# DAC_AK4493SEQ.net
KiCad netlist of a schematic drawn in Altium Designer
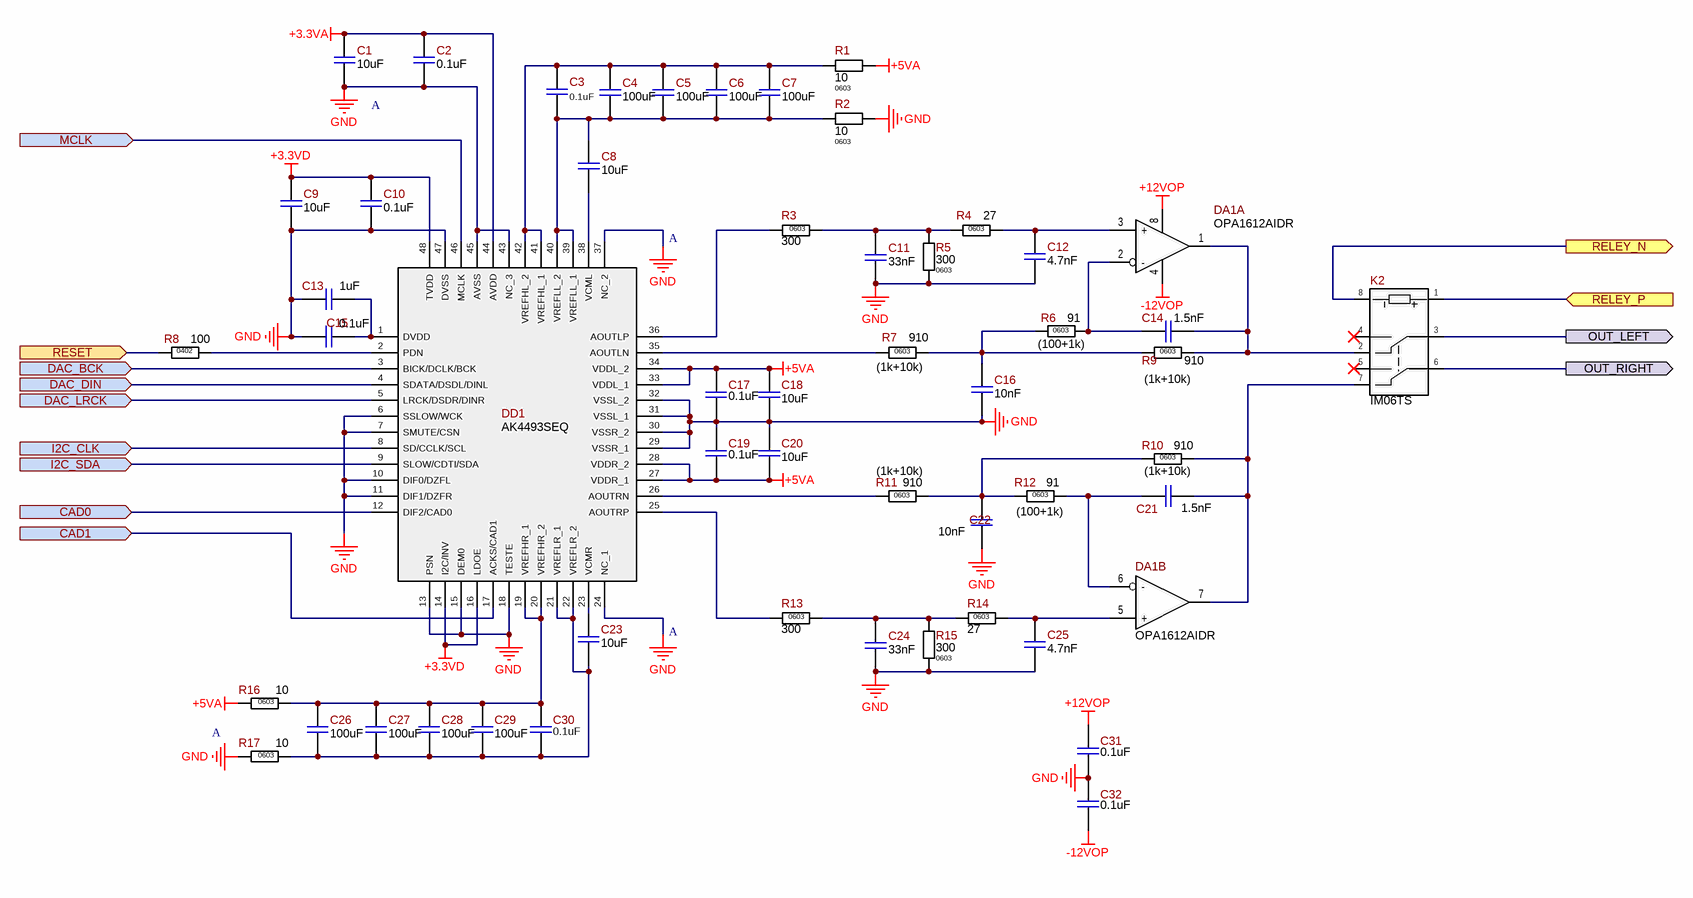
[diagram p0: DAC_AK4493SEQ.SchDoc]

(export (version "E")
  (design (tool "Eeschema 10.0.6"))
  (components
    (comp (ref "C1")
      (value "10uF")
      (footprint "C0402(1005)")
      (description "CAP CER 10UF 6.3V X6S 0402")
      (fields (field (name "PART NUMBER") "10uF  6.3V C0402") (field (name "TOLERANCE") "±20%"))
      (libsource (lib "Database") (part "Capacitor_Ceramic"))
    )
    (comp (ref "C2")
      (value "0.1uF")
      (footprint "C0402(1005)")
      (description "CAP CER 0.1UF 25V X7R 0603")
      (fields (field (name "PART NUMBER") "0.1uF  25V C0403") (field (name "TOLERANCE") "±10%"))
      (libsource (lib "Database") (part "Capacitor_Ceramic"))
    )
    (comp (ref "C3")
      (value "0.1uF")
      (footprint "C0402(1005)")
      (description "CAP CER 0.1UF 25V X7R 0603")
      (fields (field (name "PART NUMBER") "0.1uF  25V C0403") (field (name "TOLERANCE") "±10%"))
      (libsource (lib "Database") (part "Capacitor_Ceramic"))
    )
    (comp (ref "C4")
      (value "100uF")
      (footprint "C1206(3216)")
      (description "CAP CER 100UF 10V X5T 1206")
      (fields (field (name "PART NUMBER") "100uF  10V С1206") (field (name "TOLERANCE") "±20%"))
      (libsource (lib "Database") (part "Capacitor_Ceramic"))
    )
    (comp (ref "C5")
      (value "100uF")
      (footprint "C1206(3216)")
      (description "CAP CER 100UF 10V X5T 1206")
      (fields (field (name "PART NUMBER") "100uF  10V С1206") (field (name "TOLERANCE") "±20%"))
      (libsource (lib "Database") (part "Capacitor_Ceramic"))
    )
    (comp (ref "C6")
      (value "100uF")
      (footprint "C1206(3216)")
      (description "CAP CER 100UF 10V X5T 1206")
      (fields (field (name "PART NUMBER") "100uF  10V С1206") (field (name "TOLERANCE") "±20%"))
      (libsource (lib "Database") (part "Capacitor_Ceramic"))
    )
    (comp (ref "C7")
      (value "100uF")
      (footprint "C1206(3216)")
      (description "CAP CER 100UF 10V X5T 1206")
      (fields (field (name "PART NUMBER") "100uF  10V С1206") (field (name "TOLERANCE") "±20%"))
      (libsource (lib "Database") (part "Capacitor_Ceramic"))
    )
    (comp (ref "C8")
      (value "10uF")
      (footprint "C0402(1005)")
      (description "CAP CER 10UF 6.3V X6S 0402")
      (fields (field (name "PART NUMBER") "10uF  6.3V C0402") (field (name "TOLERANCE") "±20%"))
      (libsource (lib "Database") (part "Capacitor_Ceramic"))
    )
    (comp (ref "C9")
      (value "10uF")
      (footprint "C0402(1005)")
      (description "CAP CER 10UF 6.3V X6S 0402")
      (fields (field (name "PART NUMBER") "10uF  6.3V C0402") (field (name "TOLERANCE") "±20%"))
      (libsource (lib "Database") (part "Capacitor_Ceramic"))
    )
    (comp (ref "C10")
      (value "0.1uF")
      (footprint "C0402(1005)")
      (description "CAP CER 0.1UF 25V X7R 0603")
      (fields (field (name "PART NUMBER") "0.1uF  25V C0403") (field (name "TOLERANCE") "±10%"))
      (libsource (lib "Database") (part "Capacitor_Ceramic"))
    )
    (comp (ref "C11")
      (value "33nF")
      (footprint "C0603(1608)")
      (description "CAP CER 0.033UF 25V X7R 0603")
      (fields (field (name "PART NUMBER") "33nF  25V C0603") (field (name "TOLERANCE") "±20%"))
      (libsource (lib "Database") (part "Capacitor_Ceramic"))
    )
    (comp (ref "C12")
      (value "4.7nF")
      (footprint "C0603(1608)")
      (description "CAP CER 4.7nF 16V X7R 0603")
      (fields (field (name "PART NUMBER") "4.7nF  16V C0603") (field (name "TOLERANCE") "±10%"))
      (libsource (lib "Database") (part "Capacitor_Ceramic"))
    )
    (comp (ref "C13")
      (value "1uF")
      (footprint "C0402(1005)")
      (description "CAP CER 1UF 10V X7S 0402")
      (fields (field (name "PART NUMBER") "1uF  10V C0402") (field (name "TOLERANCE") "±10%"))
      (libsource (lib "Database") (part "Capacitor_Ceramic"))
    )
    (comp (ref "C14")
      (value "1.5nF")
      (footprint "C0603(1608)")
      (description "CAP CER 1.5nF 25V X7R 0603")
      (fields (field (name "PART NUMBER") "1.5nF  25V C0603") (field (name "TOLERANCE") "±10%"))
      (libsource (lib "Database") (part "Capacitor_Ceramic"))
    )
    (comp (ref "C15")
      (value "0.1uF")
      (footprint "C0402(1005)")
      (description "CAP CER 0.1UF 25V X7R 0603")
      (fields (field (name "PART NUMBER") "0.1uF  25V C0403") (field (name "TOLERANCE") "±10%"))
      (libsource (lib "Database") (part "Capacitor_Ceramic"))
    )
    (comp (ref "C16")
      (value "10nF")
      (footprint "C0603(1608)")
      (description "CAP CER 10nF 10V X5R 0603")
      (fields (field (name "PART NUMBER") "10nF  10V C0603") (field (name "TOLERANCE") "±10%"))
      (libsource (lib "Database") (part "Capacitor_Ceramic"))
    )
    (comp (ref "C17")
      (value "0.1uF")
      (footprint "C0402(1005)")
      (description "CAP CER 0.1UF 25V X7R 0603")
      (fields (field (name "PART NUMBER") "0.1uF  25V C0403") (field (name "TOLERANCE") "±10%"))
      (libsource (lib "Database") (part "Capacitor_Ceramic"))
    )
    (comp (ref "C18")
      (value "10uF")
      (footprint "C0402(1005)")
      (description "CAP CER 10UF 6.3V X6S 0402")
      (fields (field (name "PART NUMBER") "10uF  6.3V C0402") (field (name "TOLERANCE") "±20%"))
      (libsource (lib "Database") (part "Capacitor_Ceramic"))
    )
    (comp (ref "C19")
      (value "0.1uF")
      (footprint "C0402(1005)")
      (description "CAP CER 0.1UF 25V X7R 0603")
      (fields (field (name "PART NUMBER") "0.1uF  25V C0403") (field (name "TOLERANCE") "±10%"))
      (libsource (lib "Database") (part "Capacitor_Ceramic"))
    )
    (comp (ref "C20")
      (value "10uF")
      (footprint "C0402(1005)")
      (description "CAP CER 10UF 6.3V X6S 0402")
      (fields (field (name "PART NUMBER") "10uF  6.3V C0402") (field (name "TOLERANCE") "±20%"))
      (libsource (lib "Database") (part "Capacitor_Ceramic"))
    )
    (comp (ref "C21")
      (value "1.5nF")
      (footprint "C0603(1608)")
      (description "CAP CER 1.5nF 25V X7R 0603")
      (fields (field (name "PART NUMBER") "1.5nF  25V C0603") (field (name "TOLERANCE") "±10%"))
      (libsource (lib "Database") (part "Capacitor_Ceramic"))
    )
    (comp (ref "C22")
      (value "10nF")
      (footprint "C0603(1608)")
      (description "CAP CER 10nF 10V X5R 0603")
      (fields (field (name "PART NUMBER") "10nF  10V C0603") (field (name "TOLERANCE") "±10%"))
      (libsource (lib "Database") (part "Capacitor_Ceramic"))
    )
    (comp (ref "C23")
      (value "10uF")
      (footprint "C0402(1005)")
      (description "CAP CER 10UF 6.3V X6S 0402")
      (fields (field (name "PART NUMBER") "10uF  6.3V C0402") (field (name "TOLERANCE") "±20%"))
      (libsource (lib "Database") (part "Capacitor_Ceramic"))
    )
    (comp (ref "C24")
      (value "33nF")
      (footprint "C0603(1608)")
      (description "CAP CER 0.033UF 25V X7R 0603")
      (fields (field (name "PART NUMBER") "33nF  25V C0603") (field (name "TOLERANCE") "±20%"))
      (libsource (lib "Database") (part "Capacitor_Ceramic"))
    )
    (comp (ref "C25")
      (value "4.7nF")
      (footprint "C0603(1608)")
      (description "CAP CER 4.7nF 16V X7R 0603")
      (fields (field (name "PART NUMBER") "4.7nF  16V C0603") (field (name "TOLERANCE") "±10%"))
      (libsource (lib "Database") (part "Capacitor_Ceramic"))
    )
    (comp (ref "C26")
      (value "100uF")
      (footprint "C1206(3216)")
      (description "CAP CER 100UF 10V X5T 1206")
      (fields (field (name "PART NUMBER") "100uF  10V С1206") (field (name "TOLERANCE") "±20%"))
      (libsource (lib "Database") (part "Capacitor_Ceramic"))
    )
    (comp (ref "C27")
      (value "100uF")
      (footprint "C1206(3216)")
      (description "CAP CER 100UF 10V X5T 1206")
      (fields (field (name "PART NUMBER") "100uF  10V С1206") (field (name "TOLERANCE") "±20%"))
      (libsource (lib "Database") (part "Capacitor_Ceramic"))
    )
    (comp (ref "C28")
      (value "100uF")
      (footprint "C1206(3216)")
      (description "CAP CER 100UF 10V X5T 1206")
      (fields (field (name "PART NUMBER") "100uF  10V С1206") (field (name "TOLERANCE") "±20%"))
      (libsource (lib "Database") (part "Capacitor_Ceramic"))
    )
    (comp (ref "C29")
      (value "100uF")
      (footprint "C1206(3216)")
      (description "CAP CER 100UF 10V X5T 1206")
      (fields (field (name "PART NUMBER") "100uF  10V С1206") (field (name "TOLERANCE") "±20%"))
      (libsource (lib "Database") (part "Capacitor_Ceramic"))
    )
    (comp (ref "C30")
      (value "0.1uF")
      (footprint "C0402(1005)")
      (description "CAP CER 0.1UF 25V X7R 0402")
      (fields (field (name "PART NUMBER") "0.1uF  25V C0403") (field (name "TOLERANCE") "±10%"))
      (libsource (lib "Database") (part "Capacitor_Ceramic"))
    )
    (comp (ref "C31")
      (value "0.1uF")
      (footprint "C0603(1608)")
      (description "CAP CER 0.1UF 50V X7R 0603")
      (fields (field (name "PART NUMBER") "0.1uF  50V C0603") (field (name "TOLERANCE") "±10%"))
      (libsource (lib "Database") (part "Capacitor_Ceramic"))
    )
    (comp (ref "C32")
      (value "0.1uF")
      (footprint "C0603(1608)")
      (description "CAP CER 0.1UF 50V X7R 0603")
      (fields (field (name "PART NUMBER") "0.1uF  50V C0603") (field (name "TOLERANCE") "±10%"))
      (libsource (lib "Database") (part "Capacitor_Ceramic"))
    )
    (comp (ref "DA1")
      (value "OPA1612AIDR")
      (footprint "SOIC8")
      (description "Audio Amplifier 2 Circuit Rail-to-Rail 8-SOIC")
      (fields (field (name "MANUFACTURER") "Texas Instruments"))
      (libsource (lib "Database") (part "AMP8"))
    )
    (comp (ref "DD1")
      (value "AK4493SEQ")
      (footprint "LQFP48")
      (description "IC DAC/AUDIO 32BIT 768K 48LQFP (7x7)")
      (fields (field (name "MANUFACTURER") "Asahi Kasei Microdevices/AKM"))
      (libsource (lib "Database") (part "AK4493SEQ"))
    )
    (comp (ref "K2")
      (value "IM06TS")
      (footprint "IM06")
      (description "RELAY TELECOM DPDT 2A 12V coil current 11.6 mA")
      (fields (field (name "MANUFACTURER_PART_NUMBER") "HFD31/5"))
      (libsource (lib "Database") (part "IM06"))
    )
    (comp (ref "R1")
      (value "10")
      (footprint "R0603")
      (description "RES SMD 10 OHM  ±1% 1/10W 0603")
      (fields
        (field (name "PACKAGE/CASE") "0603")
        (field (name "PART NUMBER") "10  R0603")
        (field (name "TOLERANCE") "±1%")
      )
      (libsource (lib "Database") (part "R0603"))
    )
    (comp (ref "R2")
      (value "10")
      (footprint "R0603")
      (description "RES SMD 10 OHM  ±1% 1/10W 0603")
      (fields
        (field (name "PACKAGE/CASE") "0603")
        (field (name "PART NUMBER") "10  R0603")
        (field (name "TOLERANCE") "±1%")
      )
      (libsource (lib "Database") (part "R0603"))
    )
    (comp (ref "R3")
      (value "300")
      (footprint "R0603")
      (description "RES SMD 300 OHM  ±1% 1/10W 0603")
      (fields
        (field (name "PACKAGE/CASE") "0603")
        (field (name "PART NUMBER") "300  R0603")
        (field (name "TOLERANCE") "±1%")
      )
      (libsource (lib "Database") (part "R0603"))
    )
    (comp (ref "R4")
      (value "27")
      (footprint "R0603")
      (description "RES SMD 27 OHM  ±1% 1/10W 0603")
      (fields
        (field (name "PACKAGE/CASE") "0603")
        (field (name "PART NUMBER") "27  R0603")
        (field (name "TOLERANCE") "±1%")
      )
      (libsource (lib "Database") (part "R0603"))
    )
    (comp (ref "R5")
      (value "300")
      (footprint "R0603")
      (description "RES SMD 300 OHM  ±1% 1/10W 0603")
      (fields
        (field (name "PACKAGE/CASE") "0603")
        (field (name "PART NUMBER") "300  R0603")
        (field (name "TOLERANCE") "±1%")
      )
      (libsource (lib "Database") (part "R0603"))
    )
    (comp (ref "R6")
      (value "91")
      (footprint "R0603")
      (description "RES SMD 91 OHM  ±1% 1/10W 0603")
      (fields
        (field (name "PACKAGE/CASE") "0603")
        (field (name "PART NUMBER") "91  R0603")
        (field (name "TOLERANCE") "±1%")
      )
      (libsource (lib "Database") (part "R0603"))
    )
    (comp (ref "R7")
      (value "910")
      (footprint "R0603")
      (description "RES SMD 910 OHM  ±1% 1/10W 0603")
      (fields
        (field (name "PACKAGE/CASE") "0603")
        (field (name "PART NUMBER") "910  R0603")
        (field (name "TOLERANCE") "±1%")
      )
      (libsource (lib "Database") (part "R0603"))
    )
    (comp (ref "R8")
      (value "100")
      (footprint "R0402")
      (description "RES SMD 100 OHM  ±1% 1/16W 0402")
      (fields
        (field (name "PACKAGE/CASE") "0402")
        (field (name "PART NUMBER") "100  R0402")
        (field (name "TOLERANCE") "±1%")
      )
      (libsource (lib "Database") (part "R0402"))
    )
    (comp (ref "R9")
      (value "910")
      (footprint "R0603")
      (description "RES SMD 910 OHM  ±1% 1/10W 0603")
      (fields
        (field (name "PACKAGE/CASE") "0603")
        (field (name "PART NUMBER") "910  R0603")
        (field (name "TOLERANCE") "±1%")
      )
      (libsource (lib "Database") (part "R0603"))
    )
    (comp (ref "R10")
      (value "910")
      (footprint "R0603")
      (description "RES SMD 910 OHM  ±1% 1/10W 0603")
      (fields
        (field (name "PACKAGE/CASE") "0603")
        (field (name "PART NUMBER") "910  R0603")
        (field (name "TOLERANCE") "±1%")
      )
      (libsource (lib "Database") (part "R0603"))
    )
    (comp (ref "R11")
      (value "910")
      (footprint "R0603")
      (description "RES SMD 910 OHM  ±1% 1/10W 0603")
      (fields
        (field (name "PACKAGE/CASE") "0603")
        (field (name "PART NUMBER") "910  R0603")
        (field (name "TOLERANCE") "±1%")
      )
      (libsource (lib "Database") (part "R0603"))
    )
    (comp (ref "R12")
      (value "91")
      (footprint "R0603")
      (description "RES SMD 91 OHM  ±1% 1/10W 0603")
      (fields
        (field (name "PACKAGE/CASE") "0603")
        (field (name "PART NUMBER") "91  R0603")
        (field (name "TOLERANCE") "±1%")
      )
      (libsource (lib "Database") (part "R0603"))
    )
    (comp (ref "R13")
      (value "300")
      (footprint "R0603")
      (description "RES SMD 300 OHM  ±1% 1/10W 0603")
      (fields
        (field (name "PACKAGE/CASE") "0603")
        (field (name "PART NUMBER") "300  R0603")
        (field (name "TOLERANCE") "±1%")
      )
      (libsource (lib "Database") (part "R0603"))
    )
    (comp (ref "R14")
      (value "27")
      (footprint "R0603")
      (description "RES SMD 27 OHM  ±1% 1/10W 0603")
      (fields
        (field (name "PACKAGE/CASE") "0603")
        (field (name "PART NUMBER") "27  R0603")
        (field (name "TOLERANCE") "±1%")
      )
      (libsource (lib "Database") (part "R0603"))
    )
    (comp (ref "R15")
      (value "300")
      (footprint "R0603")
      (description "RES SMD 300 OHM  ±1% 1/10W 0603")
      (fields
        (field (name "PACKAGE/CASE") "0603")
        (field (name "PART NUMBER") "300  R0603")
        (field (name "TOLERANCE") "±1%")
      )
      (libsource (lib "Database") (part "R0603"))
    )
    (comp (ref "R16")
      (value "10")
      (footprint "R0603")
      (description "RES SMD 10 OHM  ±1% 1/10W 0603")
      (fields
        (field (name "PACKAGE/CASE") "0603")
        (field (name "PART NUMBER") "10  R0603")
        (field (name "TOLERANCE") "±1%")
      )
      (libsource (lib "Database") (part "R0603"))
    )
    (comp (ref "R17")
      (value "10")
      (footprint "R0603")
      (description "RES SMD 10 OHM  ±1% 1/10W 0603")
      (fields
        (field (name "PACKAGE/CASE") "0603")
        (field (name "PART NUMBER") "10  R0603")
        (field (name "TOLERANCE") "±1%")
      )
      (libsource (lib "Database") (part "R0603"))
    )
  )
  (nets
    (net (code "1") (name "+3.3VA") (class "Default")
      (node (ref "C1") (pin "1") (pinfunction "1_1") (pintype "passive"))
      (node (ref "C2") (pin "1") (pinfunction "1_1") (pintype "passive"))
      (node (ref "DD1") (pin "44") (pinfunction "AVDD_44") (pintype "passive"))
    )
    (net (code "2") (name "+3.3VD") (class "Default")
      (node (ref "C10") (pin "1") (pinfunction "1_1") (pintype "passive"))
      (node (ref "C9") (pin "1") (pinfunction "1_1") (pintype "passive"))
      (node (ref "DD1") (pin "14") (pinfunction "I2C/INV_14") (pintype "passive"))
      (node (ref "DD1") (pin "16") (pinfunction "LDOE_16") (pintype "passive"))
      (node (ref "DD1") (pin "48") (pinfunction "TVDD_48") (pintype "passive"))
    )
    (net (code "3") (name "+5VA") (class "Default")
      (node (ref "C17") (pin "1") (pinfunction "1_1") (pintype "passive"))
      (node (ref "C18") (pin "1") (pinfunction "1_1") (pintype "passive"))
      (node (ref "C19") (pin "2") (pinfunction "2_2") (pintype "passive"))
      (node (ref "C20") (pin "2") (pinfunction "2_2") (pintype "passive"))
      (node (ref "DD1") (pin "27") (pinfunction "VDDR_1_27") (pintype "passive"))
      (node (ref "DD1") (pin "28") (pinfunction "VDDR_2_28") (pintype "passive"))
      (node (ref "DD1") (pin "33") (pinfunction "VDDL_1_33") (pintype "passive"))
      (node (ref "DD1") (pin "34") (pinfunction "VDDL_2_34") (pintype "passive"))
      (node (ref "R1") (pin "2") (pinfunction "2_2") (pintype "passive"))
      (node (ref "R16") (pin "2") (pinfunction "2_2") (pintype "passive"))
    )
    (net (code "4") (name "+12VOP") (class "Default")
      (node (ref "C31") (pin "1") (pinfunction "1_1") (pintype "passive"))
      (node (ref "DA1") (pin "8") (pinfunction "V+_8") (pintype "passive"))
    )
    (net (code "5") (name "-12VOP") (class "Default")
      (node (ref "C32") (pin "2") (pinfunction "2_2") (pintype "passive"))
      (node (ref "DA1") (pin "4") (pinfunction "V-_4") (pintype "passive"))
    )
    (net (code "6") (name "/CAD0") (class "Default")
      (node (ref "DD1") (pin "12") (pinfunction "DIF2/CAD0_12") (pintype "passive"))
    )
    (net (code "7") (name "/CAD1") (class "Default")
      (node (ref "DD1") (pin "17") (pinfunction "ACKS/CAD1_17") (pintype "passive"))
    )
    (net (code "8") (name "/DAC_BCK") (class "Default")
      (node (ref "DD1") (pin "3") (pinfunction "BICK/DCLK/BCK_3") (pintype "passive"))
    )
    (net (code "9") (name "/DAC_DIN") (class "Default")
      (node (ref "DD1") (pin "4") (pinfunction "SDATA/DSDL/DINL_4") (pintype "passive"))
    )
    (net (code "10") (name "/DAC_LRCK") (class "Default")
      (node (ref "DD1") (pin "5") (pinfunction "LRCK/DSDR/DINR_5") (pintype "passive"))
    )
    (net (code "11") (name "/I2C_CLK") (class "Default")
      (node (ref "DD1") (pin "8") (pinfunction "SD/CCLK/SCL_8") (pintype "passive"))
    )
    (net (code "12") (name "/I2C_SDA") (class "Default")
      (node (ref "DD1") (pin "9") (pinfunction "SLOW/CDTI/SDA_9") (pintype "passive"))
    )
    (net (code "13") (name "/MCLK") (class "Default")
      (node (ref "DD1") (pin "46") (pinfunction "MCLK_46") (pintype "passive"))
    )
    (net (code "16") (name "/OUT_LEFT") (class "Default")
      (node (ref "K2") (pin "3") (pinfunction "1-COM_3") (pintype "passive"))
    )
    (net (code "17") (name "/OUT_RIGHT") (class "Default")
      (node (ref "K2") (pin "6") (pintype "passive"))
    )
    (net (code "18") (name "/RELEY_N") (class "Default")
      (node (ref "K2") (pin "8") (pinfunction "2-COM_8") (pintype "passive"))
    )
    (net (code "19") (name "/RELEY_P") (class "Default")
      (node (ref "K2") (pin "1") (pinfunction "Coil+_1") (pintype "passive"))
    )
    (net (code "20") (name "/RESET") (class "Default")
      (node (ref "R8") (pin "1") (pinfunction "1_1") (pintype "passive"))
    )
    (net (code "21") (name "GND") (class "Default")
      (node (ref "C1") (pin "2") (pinfunction "2_2") (pintype "passive"))
      (node (ref "C10") (pin "2") (pinfunction "2_2") (pintype "passive"))
      (node (ref "C11") (pin "1") (pinfunction "1_1") (pintype "passive"))
      (node (ref "C12") (pin "2") (pinfunction "2_2") (pintype "passive"))
      (node (ref "C13") (pin "2") (pinfunction "2_2") (pintype "passive"))
      (node (ref "C15") (pin "2") (pinfunction "2_2") (pintype "passive"))
      (node (ref "C16") (pin "2") (pinfunction "2_2") (pintype "passive"))
      (node (ref "C17") (pin "2") (pinfunction "2_2") (pintype "passive"))
      (node (ref "C18") (pin "2") (pinfunction "2_2") (pintype "passive"))
      (node (ref "C19") (pin "1") (pinfunction "1_1") (pintype "passive"))
      (node (ref "C2") (pin "2") (pinfunction "2_2") (pintype "passive"))
      (node (ref "C20") (pin "1") (pinfunction "1_1") (pintype "passive"))
      (node (ref "C22") (pin "2") (pinfunction "2_2") (pintype "passive"))
      (node (ref "C24") (pin "1") (pinfunction "1_1") (pintype "passive"))
      (node (ref "C25") (pin "2") (pinfunction "2_2") (pintype "passive"))
      (node (ref "C31") (pin "2") (pinfunction "2_2") (pintype "passive"))
      (node (ref "C32") (pin "1") (pinfunction "1_1") (pintype "passive"))
      (node (ref "C9") (pin "2") (pinfunction "2_2") (pintype "passive"))
      (node (ref "DD1") (pin "10") (pinfunction "DIF0/DZFL_10") (pintype "passive"))
      (node (ref "DD1") (pin "11") (pinfunction "DIF1/DZFR_11") (pintype "passive"))
      (node (ref "DD1") (pin "13") (pinfunction "PSN_13") (pintype "passive"))
      (node (ref "DD1") (pin "15") (pinfunction "DEM0_15") (pintype "passive"))
      (node (ref "DD1") (pin "18") (pinfunction "TESTE_18") (pintype "passive"))
      (node (ref "DD1") (pin "24") (pinfunction "NC_1_24") (pintype "passive"))
      (node (ref "DD1") (pin "29") (pinfunction "VSSR_1_29") (pintype "passive"))
      (node (ref "DD1") (pin "30") (pinfunction "VSSR_2_30") (pintype "passive"))
      (node (ref "DD1") (pin "31") (pinfunction "VSSL_1_31") (pintype "passive"))
      (node (ref "DD1") (pin "32") (pinfunction "VSSL_2_32") (pintype "passive"))
      (node (ref "DD1") (pin "37") (pinfunction "NC_2_37") (pintype "passive"))
      (node (ref "DD1") (pin "43") (pinfunction "NC_3_43") (pintype "passive"))
      (node (ref "DD1") (pin "45") (pinfunction "AVSS_45") (pintype "passive"))
      (node (ref "DD1") (pin "47") (pinfunction "DVSS_47") (pintype "passive"))
      (node (ref "DD1") (pin "6") (pinfunction "SSLOW/WCK_6") (pintype "passive"))
      (node (ref "DD1") (pin "7") (pinfunction "SMUTE/CSN_7") (pintype "passive"))
      (node (ref "R15") (pin "2") (pinfunction "2_2") (pintype "passive"))
      (node (ref "R17") (pin "2") (pinfunction "2_2") (pintype "passive"))
      (node (ref "R2") (pin "2") (pinfunction "2_2") (pintype "passive"))
      (node (ref "R5") (pin "2") (pinfunction "2_2") (pintype "passive"))
    )
    (net (code "22") (name "Net-(C11-Pad2)") (class "Default")
      (node (ref "C11") (pin "2") (pinfunction "2_2") (pintype "passive"))
      (node (ref "R3") (pin "1") (pinfunction "1_1") (pintype "passive"))
      (node (ref "R4") (pin "2") (pinfunction "2_2") (pintype "passive"))
      (node (ref "R5") (pin "1") (pinfunction "1_1") (pintype "passive"))
    )
    (net (code "23") (name "Net-(C16-Pad1)") (class "Default")
      (node (ref "C16") (pin "1") (pinfunction "1_1") (pintype "passive"))
      (node (ref "R6") (pin "1") (pinfunction "1_1") (pintype "passive"))
      (node (ref "R7") (pin "1") (pinfunction "1_1") (pintype "passive"))
      (node (ref "R9") (pin "2") (pinfunction "2_2") (pintype "passive"))
    )
    (net (code "24") (name "Net-(C22-Pad1)") (class "Default")
      (node (ref "C22") (pin "1") (pinfunction "1_1") (pintype "passive"))
      (node (ref "R10") (pin "2") (pinfunction "2_2") (pintype "passive"))
      (node (ref "R11") (pin "1") (pinfunction "1_1") (pintype "passive"))
      (node (ref "R12") (pin "2") (pinfunction "2_2") (pintype "passive"))
    )
    (net (code "25") (name "Net-(C24-Pad2)") (class "Default")
      (node (ref "C24") (pin "2") (pinfunction "2_2") (pintype "passive"))
      (node (ref "R13") (pin "1") (pinfunction "1_1") (pintype "passive"))
      (node (ref "R14") (pin "2") (pinfunction "2_2") (pintype "passive"))
      (node (ref "R15") (pin "1") (pinfunction "1_1") (pintype "passive"))
    )
    (net (code "26") (name "Net-(DA1A-+)") (class "Default")
      (node (ref "C12") (pin "1") (pinfunction "1_1") (pintype "passive"))
      (node (ref "DA1") (pin "3") (pinfunction "+_3") (pintype "passive"))
      (node (ref "R4") (pin "1") (pinfunction "1_1") (pintype "passive"))
    )
    (net (code "27") (name "Net-(DA1A--)") (class "Default")
      (node (ref "C14") (pin "2") (pinfunction "2_2") (pintype "passive"))
      (node (ref "DA1") (pin "2") (pinfunction "-_2") (pintype "passive"))
      (node (ref "R6") (pin "2") (pinfunction "2_2") (pintype "passive"))
    )
    (net (code "28") (name "Net-(DA1A-Out)") (class "Default")
      (node (ref "C14") (pin "1") (pinfunction "1_1") (pintype "passive"))
      (node (ref "DA1") (pin "1") (pinfunction "Out_1") (pintype "passive"))
      (node (ref "K2") (pin "2") (pinfunction "1-CLOSED_2") (pintype "passive"))
      (node (ref "R9") (pin "1") (pinfunction "1_1") (pintype "passive"))
    )
    (net (code "29") (name "Net-(DA1B-+)") (class "Default")
      (node (ref "C25") (pin "1") (pinfunction "1_1") (pintype "passive"))
      (node (ref "DA1") (pin "5") (pinfunction "+_5") (pintype "passive"))
      (node (ref "R14") (pin "1") (pinfunction "1_1") (pintype "passive"))
    )
    (net (code "30") (name "Net-(DA1B--)") (class "Default")
      (node (ref "C21") (pin "2") (pinfunction "2_2") (pintype "passive"))
      (node (ref "DA1") (pin "6") (pinfunction "-_6") (pintype "passive"))
      (node (ref "R12") (pin "1") (pinfunction "1_1") (pintype "passive"))
    )
    (net (code "31") (name "Net-(DA1B-Out)") (class "Default")
      (node (ref "C21") (pin "1") (pinfunction "1_1") (pintype "passive"))
      (node (ref "DA1") (pin "7") (pinfunction "Out_7") (pintype "passive"))
      (node (ref "K2") (pin "7") (pinfunction "2-OPEN_7") (pintype "passive"))
      (node (ref "R10") (pin "1") (pinfunction "1_1") (pintype "passive"))
    )
    (net (code "32") (name "Net-(DD1-AOUTLN)") (class "Default")
      (node (ref "DD1") (pin "35") (pinfunction "AOUTLN_35") (pintype "passive"))
      (node (ref "R7") (pin "2") (pinfunction "2_2") (pintype "passive"))
    )
    (net (code "33") (name "Net-(DD1-AOUTLP)") (class "Default")
      (node (ref "DD1") (pin "36") (pinfunction "AOUTLP_36") (pintype "passive"))
      (node (ref "R3") (pin "2") (pinfunction "2_2") (pintype "passive"))
    )
    (net (code "34") (name "Net-(DD1-AOUTRN)") (class "Default")
      (node (ref "DD1") (pin "26") (pinfunction "AOUTRN_26") (pintype "passive"))
      (node (ref "R11") (pin "2") (pinfunction "2_2") (pintype "passive"))
    )
    (net (code "35") (name "Net-(DD1-AOUTRP)") (class "Default")
      (node (ref "DD1") (pin "25") (pinfunction "AOUTRP_25") (pintype "passive"))
      (node (ref "R13") (pin "2") (pinfunction "2_2") (pintype "passive"))
    )
    (net (code "36") (name "Net-(DD1-DVDD)") (class "Default")
      (node (ref "C13") (pin "1") (pinfunction "1_1") (pintype "passive"))
      (node (ref "C15") (pin "1") (pinfunction "1_1") (pintype "passive"))
      (node (ref "DD1") (pin "1") (pinfunction "DVDD_1") (pintype "passive"))
    )
    (net (code "37") (name "Net-(DD1-PDN)") (class "Default")
      (node (ref "DD1") (pin "2") (pinfunction "PDN_2") (pintype "passive"))
      (node (ref "R8") (pin "2") (pinfunction "2_2") (pintype "passive"))
    )
    (net (code "38") (name "Net-(DD1-VCML)") (class "Default")
      (node (ref "C8") (pin "2") (pinfunction "2_2") (pintype "passive"))
      (node (ref "DD1") (pin "38") (pinfunction "VCML_38") (pintype "passive"))
    )
    (net (code "39") (name "Net-(DD1-VCMR)") (class "Default")
      (node (ref "C23") (pin "1") (pinfunction "1_1") (pintype "passive"))
      (node (ref "DD1") (pin "23") (pinfunction "VCMR_23") (pintype "passive"))
    )
    (net (code "40") (name "Net-(DD1-VREFHL_1)") (class "Default")
      (node (ref "C3") (pin "1") (pinfunction "1_1") (pintype "passive"))
      (node (ref "C4") (pin "2") (pinfunction "2_2") (pintype "passive"))
      (node (ref "C5") (pin "2") (pinfunction "2_2") (pintype "passive"))
      (node (ref "C6") (pin "2") (pinfunction "2_2") (pintype "passive"))
      (node (ref "C7") (pin "2") (pinfunction "2_2") (pintype "passive"))
      (node (ref "DD1") (pin "41") (pinfunction "VREFHL_1_41") (pintype "passive"))
      (node (ref "DD1") (pin "42") (pinfunction "VREFHL_2_42") (pintype "passive"))
      (node (ref "R1") (pin "1") (pinfunction "1_1") (pintype "passive"))
    )
    (net (code "41") (name "Net-(DD1-VREFHR_1)") (class "Default")
      (node (ref "C26") (pin "1") (pinfunction "1_1") (pintype "passive"))
      (node (ref "C27") (pin "1") (pinfunction "1_1") (pintype "passive"))
      (node (ref "C28") (pin "1") (pinfunction "1_1") (pintype "passive"))
      (node (ref "C29") (pin "1") (pinfunction "1_1") (pintype "passive"))
      (node (ref "C30") (pin "1") (pinfunction "1_1") (pintype "passive"))
      (node (ref "DD1") (pin "19") (pinfunction "VREFHR_1_19") (pintype "passive"))
      (node (ref "DD1") (pin "20") (pinfunction "VREFHR_2_20") (pintype "passive"))
      (node (ref "R16") (pin "1") (pinfunction "1_1") (pintype "passive"))
    )
    (net (code "42") (name "Net-(DD1-VREFLL_1)") (class "Default")
      (node (ref "C3") (pin "2") (pinfunction "2_2") (pintype "passive"))
      (node (ref "C4") (pin "1") (pinfunction "1_1") (pintype "passive"))
      (node (ref "C5") (pin "1") (pinfunction "1_1") (pintype "passive"))
      (node (ref "C6") (pin "1") (pinfunction "1_1") (pintype "passive"))
      (node (ref "C7") (pin "1") (pinfunction "1_1") (pintype "passive"))
      (node (ref "C8") (pin "1") (pinfunction "1_1") (pintype "passive"))
      (node (ref "DD1") (pin "39") (pinfunction "VREFLL_1_39") (pintype "passive"))
      (node (ref "DD1") (pin "40") (pinfunction "VREFLL_2_40") (pintype "passive"))
      (node (ref "R2") (pin "1") (pinfunction "1_1") (pintype "passive"))
    )
    (net (code "43") (name "Net-(DD1-VREFLR_1)") (class "Default")
      (node (ref "C23") (pin "2") (pinfunction "2_2") (pintype "passive"))
      (node (ref "C26") (pin "2") (pinfunction "2_2") (pintype "passive"))
      (node (ref "C27") (pin "2") (pinfunction "2_2") (pintype "passive"))
      (node (ref "C28") (pin "2") (pinfunction "2_2") (pintype "passive"))
      (node (ref "C29") (pin "2") (pinfunction "2_2") (pintype "passive"))
      (node (ref "C30") (pin "2") (pinfunction "2_2") (pintype "passive"))
      (node (ref "DD1") (pin "21") (pinfunction "VREFLR_1_21") (pintype "passive"))
      (node (ref "DD1") (pin "22") (pinfunction "VREFLR_2_22") (pintype "passive"))
      (node (ref "R17") (pin "1") (pinfunction "1_1") (pintype "passive"))
    )
    (net (code "44") (name "unconnected-(K2-1-OPEN-Pad4)") (class "Default")
      (node (ref "K2") (pin "4") (pinfunction "1-OPEN_4") (pintype "passive+no_connect"))
    )
    (net (code "45") (name "unconnected-(K2-Pad5)") (class "Default")
      (node (ref "K2") (pin "5") (pintype "passive+no_connect"))
    )
  )
)
